# EXPENSION.net
KiCad netlist of a schematic drawn in Altium Designer
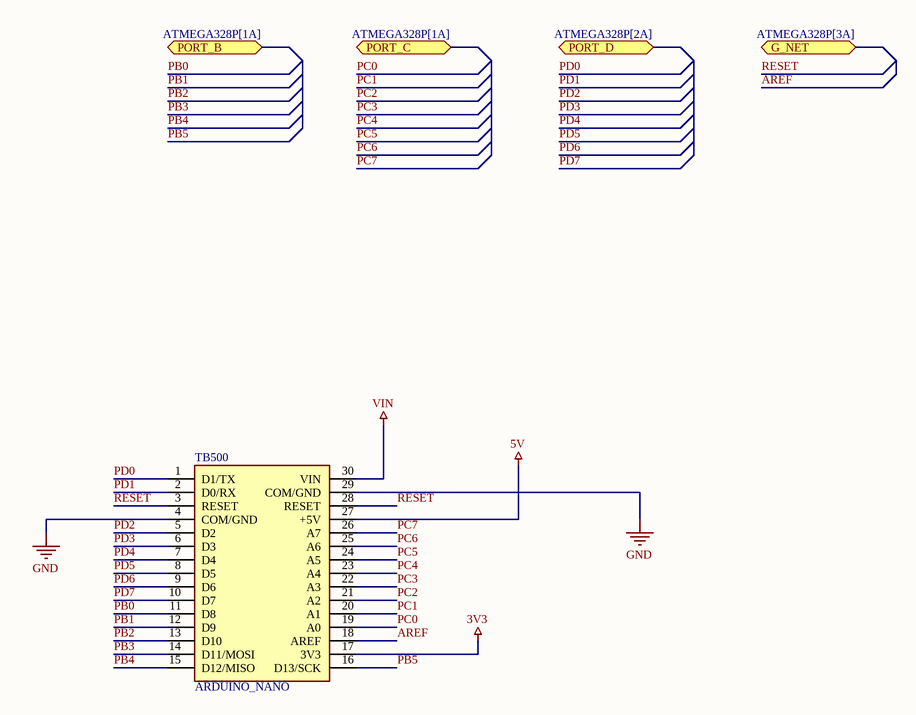
[diagram p0: EXPENSION.SchDoc]

(export (version "E")
  (design (tool "Eeschema 10.0.6"))
  (components
    (comp (ref "TB500")
      (value "ARDUINO_NANO")
      (footprint "SHIELD_ARDUINO_NANO")
      (description "Small, complete, and breadboard-friendly board based on the ATmega328 (Arduino Nano 3.x)")
      (fields (field (name "MF") "Arduino") (field (name "MP") "Arduino Nano"))
      (libsource (lib "ARDUINO_NANO") (part "ARDUINO_NANO"))
    )
  )
  (nets
    (net (code "1") (name "/AREF") (class "Default")
      (node (ref "TB500") (pin "18") (pinfunction "AREF_18") (pintype "power_in"))
    )
    (net (code "3") (name "/PB0") (class "Default")
      (node (ref "TB500") (pin "11") (pinfunction "D8_11") (pintype "open_collector"))
    )
    (net (code "4") (name "/PB1") (class "Default")
      (node (ref "TB500") (pin "12") (pinfunction "D9_12") (pintype "open_collector"))
    )
    (net (code "5") (name "/PB2") (class "Default")
      (node (ref "TB500") (pin "13") (pinfunction "D10_13") (pintype "open_collector"))
    )
    (net (code "6") (name "/PB3") (class "Default")
      (node (ref "TB500") (pin "14") (pinfunction "D11/MOSI_14") (pintype "open_collector"))
    )
    (net (code "7") (name "/PB4") (class "Default")
      (node (ref "TB500") (pin "15") (pinfunction "D12/MISO_15") (pintype "open_collector"))
    )
    (net (code "8") (name "/PB5") (class "Default")
      (node (ref "TB500") (pin "16") (pinfunction "D13/SCK_16") (pintype "open_collector"))
    )
    (net (code "9") (name "/PC0") (class "Default")
      (node (ref "TB500") (pin "19") (pinfunction "A0_19") (pintype "open_collector"))
    )
    (net (code "10") (name "/PC1") (class "Default")
      (node (ref "TB500") (pin "20") (pinfunction "A1_20") (pintype "open_collector"))
    )
    (net (code "11") (name "/PC2") (class "Default")
      (node (ref "TB500") (pin "21") (pinfunction "A2_21") (pintype "open_collector"))
    )
    (net (code "12") (name "/PC3") (class "Default")
      (node (ref "TB500") (pin "22") (pinfunction "A3_22") (pintype "open_collector"))
    )
    (net (code "13") (name "/PC4") (class "Default")
      (node (ref "TB500") (pin "23") (pinfunction "A4_23") (pintype "open_collector"))
    )
    (net (code "14") (name "/PC5") (class "Default")
      (node (ref "TB500") (pin "24") (pinfunction "A5_24") (pintype "open_collector"))
    )
    (net (code "15") (name "/PC6") (class "Default")
      (node (ref "TB500") (pin "25") (pinfunction "A6_25") (pintype "open_collector"))
    )
    (net (code "16") (name "/PC7") (class "Default")
      (node (ref "TB500") (pin "26") (pinfunction "A7_26") (pintype "open_collector"))
    )
    (net (code "17") (name "/PD0") (class "Default")
      (node (ref "TB500") (pin "1") (pinfunction "D1/TX_1") (pintype "open_collector"))
    )
    (net (code "18") (name "/PD1") (class "Default")
      (node (ref "TB500") (pin "2") (pinfunction "D0/RX_2") (pintype "open_collector"))
    )
    (net (code "19") (name "/PD2") (class "Default")
      (node (ref "TB500") (pin "5") (pinfunction "D2_5") (pintype "open_collector"))
    )
    (net (code "20") (name "/PD3") (class "Default")
      (node (ref "TB500") (pin "6") (pinfunction "D3_6") (pintype "open_collector"))
    )
    (net (code "21") (name "/PD4") (class "Default")
      (node (ref "TB500") (pin "7") (pinfunction "D4_7") (pintype "open_collector"))
    )
    (net (code "22") (name "/PD5") (class "Default")
      (node (ref "TB500") (pin "8") (pinfunction "D5_8") (pintype "open_collector"))
    )
    (net (code "23") (name "/PD6") (class "Default")
      (node (ref "TB500") (pin "9") (pinfunction "D6_9") (pintype "open_collector"))
    )
    (net (code "24") (name "/PD7") (class "Default")
      (node (ref "TB500") (pin "10") (pinfunction "D7_10") (pintype "open_collector"))
    )
    (net (code "28") (name "/RESET") (class "Default")
      (node (ref "TB500") (pin "28") (pinfunction "RESET_28") (pintype "open_collector"))
      (node (ref "TB500") (pin "3") (pinfunction "RESET_3") (pintype "open_collector"))
    )
    (net (code "29") (name "3V3") (class "Default")
      (node (ref "TB500") (pin "17") (pinfunction "3V3_17") (pintype "power_in"))
    )
    (net (code "30") (name "5V") (class "Default")
      (node (ref "TB500") (pin "27") (pinfunction "+5V_27") (pintype "power_in"))
    )
    (net (code "31") (name "GND") (class "Default")
      (node (ref "TB500") (pin "29") (pinfunction "COM/GND_29") (pintype "power_in"))
      (node (ref "TB500") (pin "4") (pinfunction "COM/GND_4") (pintype "power_in"))
    )
    (net (code "32") (name "VIN") (class "Default")
      (node (ref "TB500") (pin "30") (pinfunction "VIN_30") (pintype "open_collector"))
    )
  )
)
